# MCU.net
KiCad netlist of a schematic drawn in Altium Designer
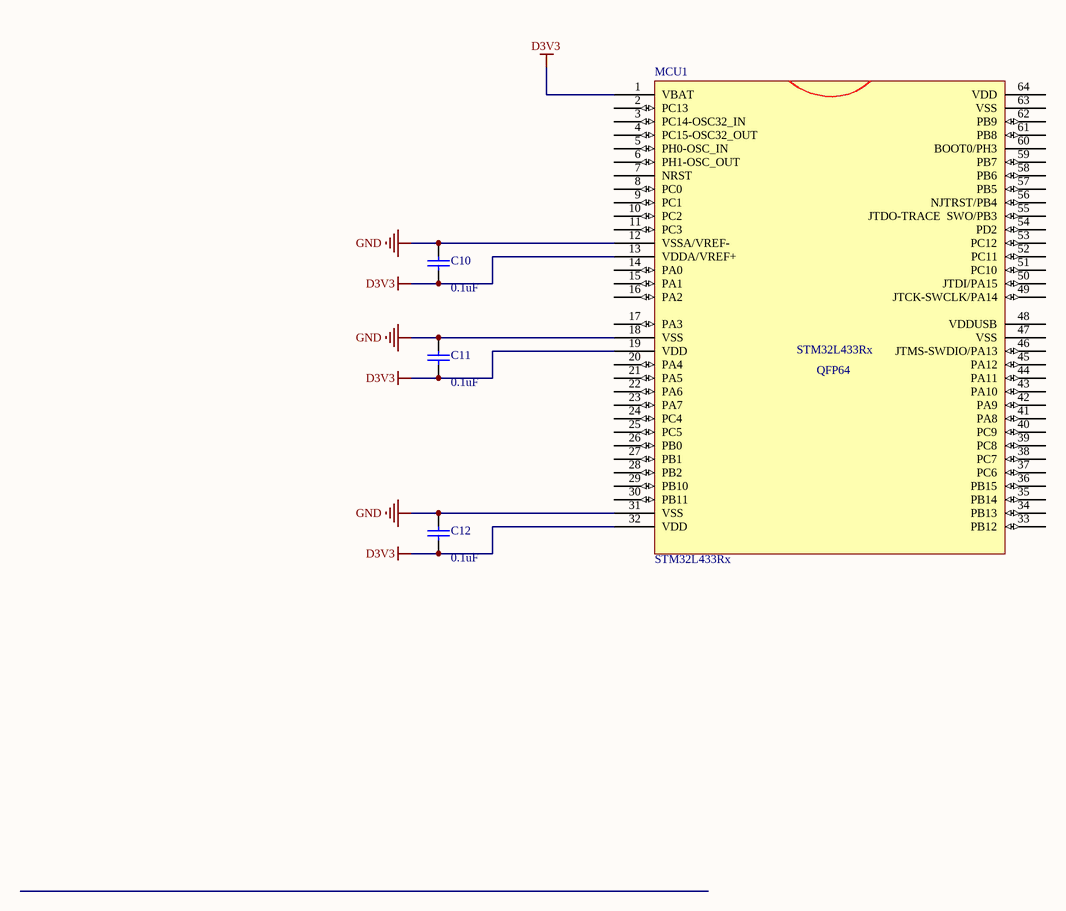
[diagram p0: MCU.SchDoc]

(export (version "E")
  (design (tool "Eeschema 10.0.6"))
  (components
    (comp (ref "C10")
      (value "0.1uF")
      (footprint "C1206")
      (description "Capacitor (Semiconductor SIM Model)")
      (fields (field (name "PUBLISHER") "Altium Limited"))
      (libsource (lib "Miscellaneous Devices") (part "Cap Semi"))
    )
    (comp (ref "C11")
      (value "0.1uF")
      (footprint "C1206")
      (description "Capacitor (Semiconductor SIM Model)")
      (fields (field (name "PUBLISHER") "Altium Limited"))
      (libsource (lib "Miscellaneous Devices") (part "Cap Semi"))
    )
    (comp (ref "C12")
      (value "0.1uF")
      (footprint "C1206")
      (description "Capacitor (Semiconductor SIM Model)")
      (fields (field (name "PUBLISHER") "Altium Limited"))
      (libsource (lib "Miscellaneous Devices") (part "Cap Semi"))
    )
    (comp (ref "MCU1")
      (value "STM32L433Rx")
      (footprint "LQFP64")
      (description "超低功耗高性能ARM Cortex-M4 32-bit MCU+FPU 80MHz 100DMIPS")
      (libsource (lib "BearPi_RevB01") (part "STM32L433Rx"))
    )
  )
  (nets
    (net (code "1") (name "D3V3") (class "Default")
      (node (ref "C10") (pin "2") (pinfunction "2_2") (pintype "passive"))
      (node (ref "C11") (pin "2") (pinfunction "2_2") (pintype "passive"))
      (node (ref "C12") (pin "2") (pinfunction "2_2") (pintype "passive"))
      (node (ref "MCU1") (pin "1") (pinfunction "VBAT_1") (pintype "passive"))
      (node (ref "MCU1") (pin "13") (pinfunction "VDDA/VREF+_13") (pintype "passive"))
      (node (ref "MCU1") (pin "19") (pinfunction "VDD_19") (pintype "passive"))
      (node (ref "MCU1") (pin "32") (pinfunction "VDD_32") (pintype "passive"))
    )
    (net (code "2") (name "GND") (class "Default")
      (node (ref "C10") (pin "1") (pinfunction "1_1") (pintype "passive"))
      (node (ref "C11") (pin "1") (pinfunction "1_1") (pintype "passive"))
      (node (ref "C12") (pin "1") (pinfunction "1_1") (pintype "passive"))
      (node (ref "MCU1") (pin "12") (pinfunction "VSSA/VREF-_12") (pintype "passive"))
      (node (ref "MCU1") (pin "18") (pinfunction "VSS_18") (pintype "passive"))
      (node (ref "MCU1") (pin "31") (pinfunction "VSS_31") (pintype "passive"))
    )
    (net (code "3") (name "unconnected-(MCU1-BOOT0{slash}PH3-Pad60)") (class "Default")
      (node (ref "MCU1") (pin "60") (pinfunction "BOOT0/PH3_60") (pintype "passive"))
    )
    (net (code "4") (name "unconnected-(MCU1-JTCK-SWCLK{slash}PA14-Pad49)") (class "Default")
      (node (ref "MCU1") (pin "49") (pinfunction "JTCK-SWCLK/PA14_49") (pintype "bidirectional"))
    )
    (net (code "5") (name "unconnected-(MCU1-JTDI{slash}PA15-Pad50)") (class "Default")
      (node (ref "MCU1") (pin "50") (pinfunction "JTDI/PA15_50") (pintype "bidirectional"))
    )
    (net (code "6") (name "unconnected-(MCU1-JTDO-TRACE__SWO{slash}PB3-Pad55)") (class "Default")
      (node (ref "MCU1") (pin "55") (pinfunction "JTDO-TRACE__SWO/PB3_55") (pintype "bidirectional"))
    )
    (net (code "7") (name "unconnected-(MCU1-JTMS-SWDIO{slash}PA13-Pad46)") (class "Default")
      (node (ref "MCU1") (pin "46") (pinfunction "JTMS-SWDIO/PA13_46") (pintype "bidirectional"))
    )
    (net (code "8") (name "unconnected-(MCU1-NJTRST{slash}PB4-Pad56)") (class "Default")
      (node (ref "MCU1") (pin "56") (pinfunction "NJTRST/PB4_56") (pintype "bidirectional"))
    )
    (net (code "9") (name "unconnected-(MCU1-NRST-Pad7)") (class "Default")
      (node (ref "MCU1") (pin "7") (pinfunction "NRST_7") (pintype "passive"))
    )
    (net (code "10") (name "unconnected-(MCU1-PA0-Pad14)") (class "Default")
      (node (ref "MCU1") (pin "14") (pinfunction "PA0_14") (pintype "bidirectional"))
    )
    (net (code "11") (name "unconnected-(MCU1-PA1-Pad15)") (class "Default")
      (node (ref "MCU1") (pin "15") (pinfunction "PA1_15") (pintype "bidirectional"))
    )
    (net (code "12") (name "unconnected-(MCU1-PA2-Pad16)") (class "Default")
      (node (ref "MCU1") (pin "16") (pinfunction "PA2_16") (pintype "bidirectional"))
    )
    (net (code "13") (name "unconnected-(MCU1-PA3-Pad17)") (class "Default")
      (node (ref "MCU1") (pin "17") (pinfunction "PA3_17") (pintype "bidirectional"))
    )
    (net (code "14") (name "unconnected-(MCU1-PA4-Pad20)") (class "Default")
      (node (ref "MCU1") (pin "20") (pinfunction "PA4_20") (pintype "bidirectional"))
    )
    (net (code "15") (name "unconnected-(MCU1-PA5-Pad21)") (class "Default")
      (node (ref "MCU1") (pin "21") (pinfunction "PA5_21") (pintype "bidirectional"))
    )
    (net (code "16") (name "unconnected-(MCU1-PA6-Pad22)") (class "Default")
      (node (ref "MCU1") (pin "22") (pinfunction "PA6_22") (pintype "bidirectional"))
    )
    (net (code "17") (name "unconnected-(MCU1-PA7-Pad23)") (class "Default")
      (node (ref "MCU1") (pin "23") (pinfunction "PA7_23") (pintype "bidirectional"))
    )
    (net (code "18") (name "unconnected-(MCU1-PA8-Pad41)") (class "Default")
      (node (ref "MCU1") (pin "41") (pinfunction "PA8_41") (pintype "bidirectional"))
    )
    (net (code "19") (name "unconnected-(MCU1-PA9-Pad42)") (class "Default")
      (node (ref "MCU1") (pin "42") (pinfunction "PA9_42") (pintype "bidirectional"))
    )
    (net (code "20") (name "unconnected-(MCU1-PA10-Pad43)") (class "Default")
      (node (ref "MCU1") (pin "43") (pinfunction "PA10_43") (pintype "bidirectional"))
    )
    (net (code "21") (name "unconnected-(MCU1-PA11-Pad44)") (class "Default")
      (node (ref "MCU1") (pin "44") (pinfunction "PA11_44") (pintype "bidirectional"))
    )
    (net (code "22") (name "unconnected-(MCU1-PA12-Pad45)") (class "Default")
      (node (ref "MCU1") (pin "45") (pinfunction "PA12_45") (pintype "bidirectional"))
    )
    (net (code "23") (name "unconnected-(MCU1-PB0-Pad26)") (class "Default")
      (node (ref "MCU1") (pin "26") (pinfunction "PB0_26") (pintype "bidirectional"))
    )
    (net (code "24") (name "unconnected-(MCU1-PB1-Pad27)") (class "Default")
      (node (ref "MCU1") (pin "27") (pinfunction "PB1_27") (pintype "bidirectional"))
    )
    (net (code "25") (name "unconnected-(MCU1-PB2-Pad28)") (class "Default")
      (node (ref "MCU1") (pin "28") (pinfunction "PB2_28") (pintype "bidirectional"))
    )
    (net (code "26") (name "unconnected-(MCU1-PB5-Pad57)") (class "Default")
      (node (ref "MCU1") (pin "57") (pinfunction "PB5_57") (pintype "bidirectional"))
    )
    (net (code "27") (name "unconnected-(MCU1-PB6-Pad58)") (class "Default")
      (node (ref "MCU1") (pin "58") (pinfunction "PB6_58") (pintype "bidirectional"))
    )
    (net (code "28") (name "unconnected-(MCU1-PB7-Pad59)") (class "Default")
      (node (ref "MCU1") (pin "59") (pinfunction "PB7_59") (pintype "bidirectional"))
    )
    (net (code "29") (name "unconnected-(MCU1-PB8-Pad61)") (class "Default")
      (node (ref "MCU1") (pin "61") (pinfunction "PB8_61") (pintype "bidirectional"))
    )
    (net (code "30") (name "unconnected-(MCU1-PB9-Pad62)") (class "Default")
      (node (ref "MCU1") (pin "62") (pinfunction "PB9_62") (pintype "bidirectional"))
    )
    (net (code "31") (name "unconnected-(MCU1-PB10-Pad29)") (class "Default")
      (node (ref "MCU1") (pin "29") (pinfunction "PB10_29") (pintype "bidirectional"))
    )
    (net (code "32") (name "unconnected-(MCU1-PB11-Pad30)") (class "Default")
      (node (ref "MCU1") (pin "30") (pinfunction "PB11_30") (pintype "bidirectional"))
    )
    (net (code "33") (name "unconnected-(MCU1-PB12-Pad33)") (class "Default")
      (node (ref "MCU1") (pin "33") (pinfunction "PB12_33") (pintype "bidirectional"))
    )
    (net (code "34") (name "unconnected-(MCU1-PB13-Pad34)") (class "Default")
      (node (ref "MCU1") (pin "34") (pinfunction "PB13_34") (pintype "bidirectional"))
    )
    (net (code "35") (name "unconnected-(MCU1-PB14-Pad35)") (class "Default")
      (node (ref "MCU1") (pin "35") (pinfunction "PB14_35") (pintype "bidirectional"))
    )
    (net (code "36") (name "unconnected-(MCU1-PB15-Pad36)") (class "Default")
      (node (ref "MCU1") (pin "36") (pinfunction "PB15_36") (pintype "bidirectional"))
    )
    (net (code "37") (name "unconnected-(MCU1-PC0-Pad8)") (class "Default")
      (node (ref "MCU1") (pin "8") (pinfunction "PC0_8") (pintype "bidirectional"))
    )
    (net (code "38") (name "unconnected-(MCU1-PC1-Pad9)") (class "Default")
      (node (ref "MCU1") (pin "9") (pinfunction "PC1_9") (pintype "bidirectional"))
    )
    (net (code "39") (name "unconnected-(MCU1-PC2-Pad10)") (class "Default")
      (node (ref "MCU1") (pin "10") (pinfunction "PC2_10") (pintype "bidirectional"))
    )
    (net (code "40") (name "unconnected-(MCU1-PC3-Pad11)") (class "Default")
      (node (ref "MCU1") (pin "11") (pinfunction "PC3_11") (pintype "bidirectional"))
    )
    (net (code "41") (name "unconnected-(MCU1-PC4-Pad24)") (class "Default")
      (node (ref "MCU1") (pin "24") (pinfunction "PC4_24") (pintype "bidirectional"))
    )
    (net (code "42") (name "unconnected-(MCU1-PC5-Pad25)") (class "Default")
      (node (ref "MCU1") (pin "25") (pinfunction "PC5_25") (pintype "bidirectional"))
    )
    (net (code "43") (name "unconnected-(MCU1-PC6-Pad37)") (class "Default")
      (node (ref "MCU1") (pin "37") (pinfunction "PC6_37") (pintype "bidirectional"))
    )
    (net (code "44") (name "unconnected-(MCU1-PC7-Pad38)") (class "Default")
      (node (ref "MCU1") (pin "38") (pinfunction "PC7_38") (pintype "bidirectional"))
    )
    (net (code "45") (name "unconnected-(MCU1-PC8-Pad39)") (class "Default")
      (node (ref "MCU1") (pin "39") (pinfunction "PC8_39") (pintype "bidirectional"))
    )
    (net (code "46") (name "unconnected-(MCU1-PC9-Pad40)") (class "Default")
      (node (ref "MCU1") (pin "40") (pinfunction "PC9_40") (pintype "bidirectional"))
    )
    (net (code "47") (name "unconnected-(MCU1-PC10-Pad51)") (class "Default")
      (node (ref "MCU1") (pin "51") (pinfunction "PC10_51") (pintype "bidirectional"))
    )
    (net (code "48") (name "unconnected-(MCU1-PC11-Pad52)") (class "Default")
      (node (ref "MCU1") (pin "52") (pinfunction "PC11_52") (pintype "bidirectional"))
    )
    (net (code "49") (name "unconnected-(MCU1-PC12-Pad53)") (class "Default")
      (node (ref "MCU1") (pin "53") (pinfunction "PC12_53") (pintype "bidirectional"))
    )
    (net (code "50") (name "unconnected-(MCU1-PC13-Pad2)") (class "Default")
      (node (ref "MCU1") (pin "2") (pinfunction "PC13_2") (pintype "bidirectional"))
    )
    (net (code "51") (name "unconnected-(MCU1-PC14-OSC32_IN-Pad3)") (class "Default")
      (node (ref "MCU1") (pin "3") (pinfunction "PC14-OSC32_IN_3") (pintype "bidirectional"))
    )
    (net (code "52") (name "unconnected-(MCU1-PC15-OSC32_OUT-Pad4)") (class "Default")
      (node (ref "MCU1") (pin "4") (pinfunction "PC15-OSC32_OUT_4") (pintype "bidirectional"))
    )
    (net (code "53") (name "unconnected-(MCU1-PD2-Pad54)") (class "Default")
      (node (ref "MCU1") (pin "54") (pinfunction "PD2_54") (pintype "bidirectional"))
    )
    (net (code "54") (name "unconnected-(MCU1-PH0-OSC_IN-Pad5)") (class "Default")
      (node (ref "MCU1") (pin "5") (pinfunction "PH0-OSC_IN_5") (pintype "bidirectional"))
    )
    (net (code "55") (name "unconnected-(MCU1-PH1-OSC_OUT-Pad6)") (class "Default")
      (node (ref "MCU1") (pin "6") (pinfunction "PH1-OSC_OUT_6") (pintype "bidirectional"))
    )
    (net (code "56") (name "unconnected-(MCU1-VDD-Pad64)") (class "Default")
      (node (ref "MCU1") (pin "64") (pinfunction "VDD_64") (pintype "passive"))
    )
    (net (code "57") (name "unconnected-(MCU1-VDDUSB-Pad48)") (class "Default")
      (node (ref "MCU1") (pin "48") (pinfunction "VDDUSB_48") (pintype "passive"))
    )
    (net (code "58") (name "unconnected-(MCU1-VSS-Pad47)") (class "Default")
      (node (ref "MCU1") (pin "47") (pinfunction "VSS_47") (pintype "passive"))
    )
    (net (code "59") (name "unconnected-(MCU1-VSS-Pad63)") (class "Default")
      (node (ref "MCU1") (pin "63") (pinfunction "VSS_63") (pintype "passive"))
    )
  )
)
